# Adafruit_Ultimate_GPS.net
KiCad netlist of a schematic drawn in EAGLE
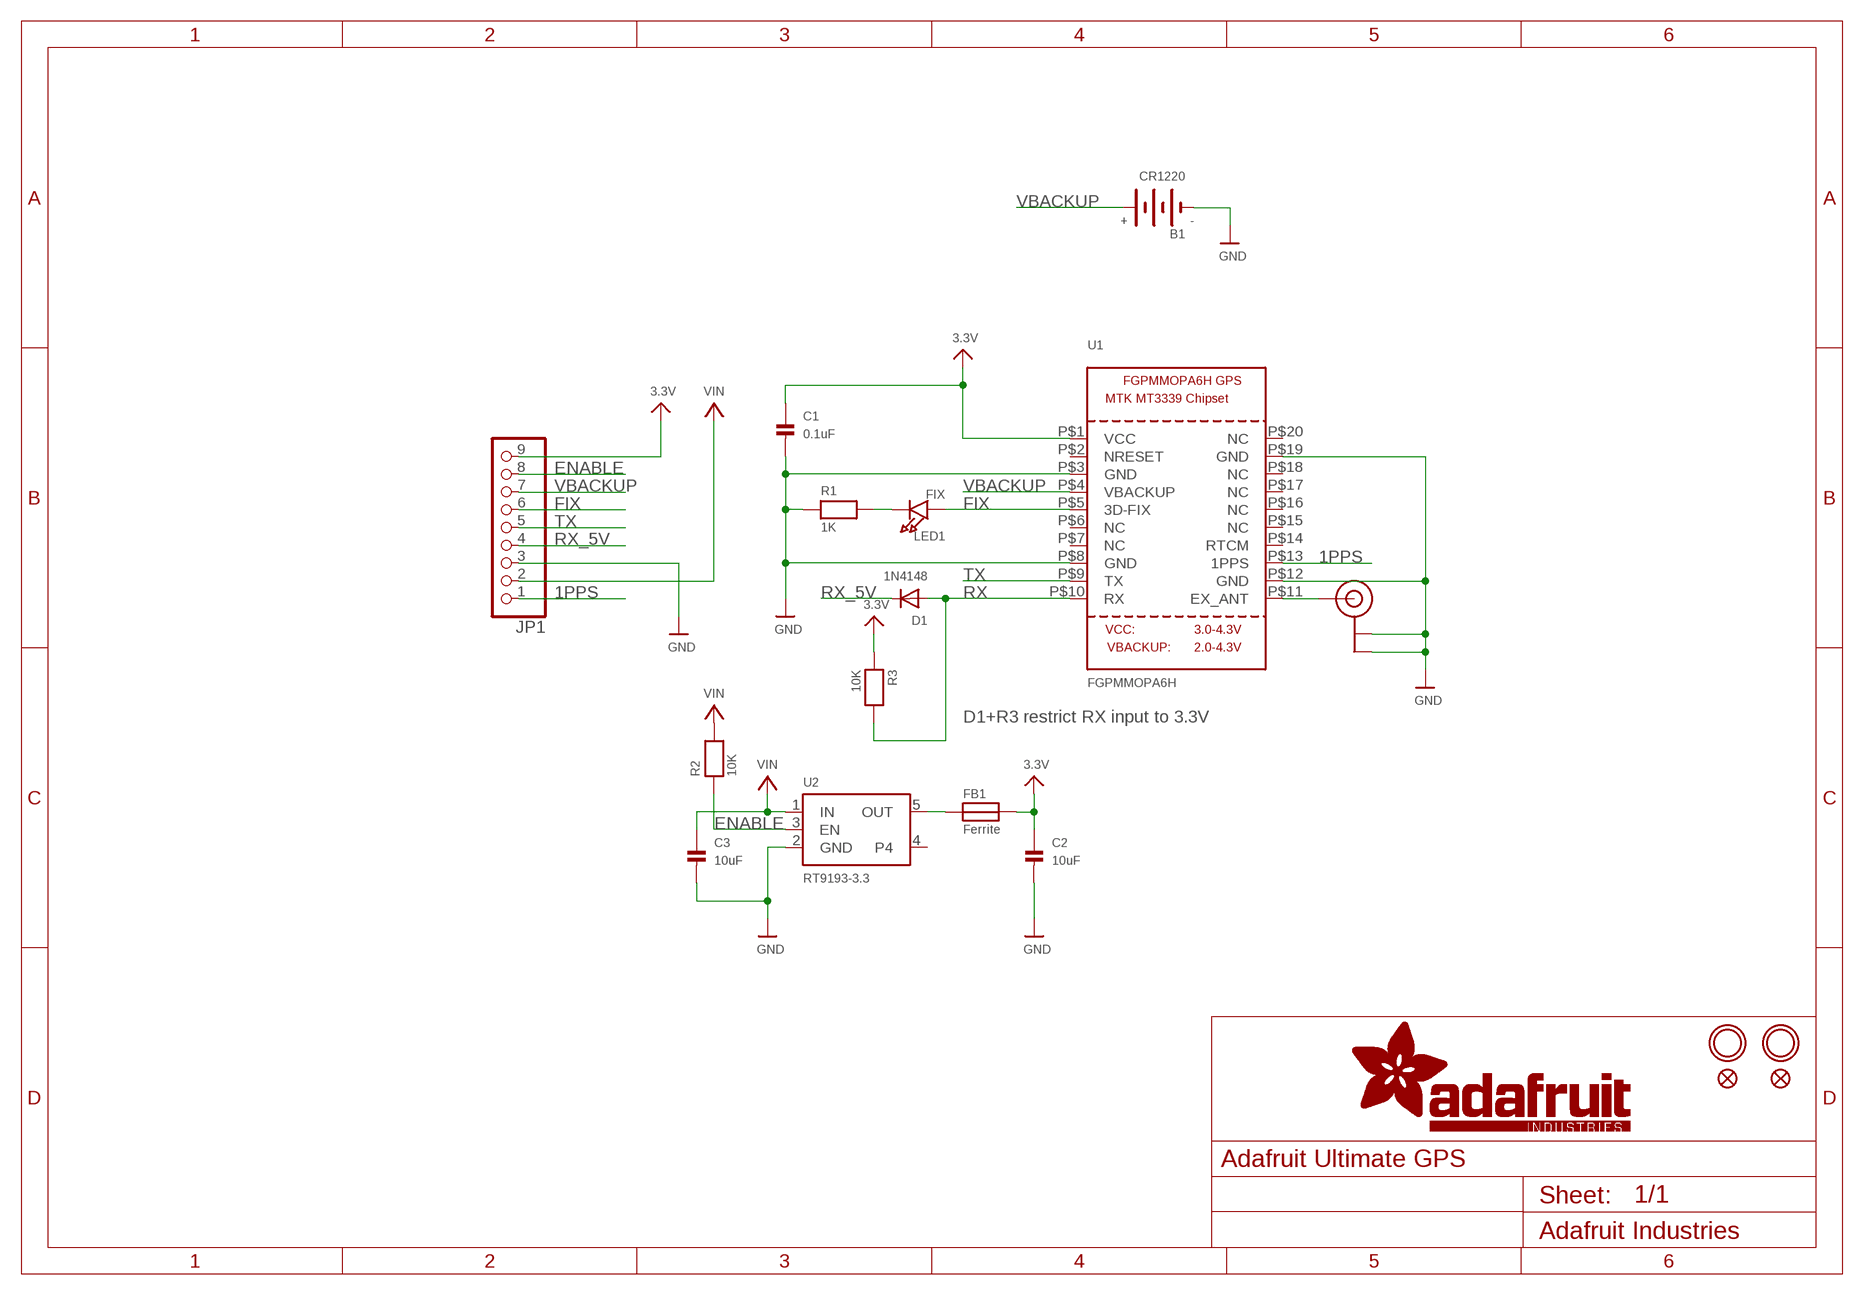
[diagram p0: schematic, sheet 1]

(export (version "E")
  (design (tool "Eeschema 10.0.6"))
  (components
    (comp (ref "B1")
      (value "CR1220")
      (footprint "eagle-import:CR1220")
      (libsource (lib "eagle-import") (part "BATTERYCR1220_SMT"))
    )
    (comp (ref "C1")
      (value "0.1uF")
      (footprint "eagle-import:0805")
      (libsource (lib "eagle-import") (part "CAP_CERAMIC0805"))
    )
    (comp (ref "C2")
      (value "10uF")
      (footprint "eagle-import:0805")
      (libsource (lib "eagle-import") (part "CAP_CERAMIC0805"))
    )
    (comp (ref "C3")
      (value "10uF")
      (footprint "eagle-import:0805")
      (libsource (lib "eagle-import") (part "CAP_CERAMIC0805"))
    )
    (comp (ref "D1")
      (value "1N4148")
      (footprint "eagle-import:SOD-323F")
      (libsource (lib "eagle-import") (part "DIODESOD-323F"))
    )
    (comp (ref "FB1")
      (value "Ferrite")
      (footprint "eagle-import:0805")
      (libsource (lib "eagle-import") (part "FERRITE0805"))
    )
    (comp (ref "FID1")
      (value "FIDUCIAL\"\"")
      (footprint "eagle-import:FIDUCIAL_1MM")
      (libsource (lib "eagle-import") (part "FIDUCIAL{dblquote}{dblquote}"))
    )
    (comp (ref "FID2")
      (value "FIDUCIAL\"\"")
      (footprint "eagle-import:FIDUCIAL_1MM")
      (libsource (lib "eagle-import") (part "FIDUCIAL{dblquote}{dblquote}"))
    )
    (comp (ref "JP1")
      (value "HEADER-1X970MIL")
      (footprint "eagle-import:1X09_ROUND_70")
      (libsource (lib "eagle-import") (part "HEADER-1X970MIL"))
    )
    (comp (ref "LED1")
      (value "FIX")
      (footprint "eagle-import:CHIPLED_0805")
      (libsource (lib "eagle-import") (part "LED0805"))
    )
    (comp (ref "R1")
      (value "1K")
      (footprint "eagle-import:0805")
      (libsource (lib "eagle-import") (part "RESISTOR0805"))
    )
    (comp (ref "R2")
      (value "10K")
      (footprint "eagle-import:0805")
      (libsource (lib "eagle-import") (part "RESISTOR0805"))
    )
    (comp (ref "R3")
      (value "10K")
      (footprint "eagle-import:0805")
      (libsource (lib "eagle-import") (part "RESISTOR0805"))
    )
    (comp (ref "U$8")
      (value "MOUNTINGHOLE2.0")
      (footprint "eagle-import:MOUNTINGHOLE_2.0_PLATED")
      (libsource (lib "eagle-import") (part "MOUNTINGHOLE2.0"))
    )
    (comp (ref "U$9")
      (value "MOUNTINGHOLE2.0")
      (footprint "eagle-import:MOUNTINGHOLE_2.0_PLATED")
      (libsource (lib "eagle-import") (part "MOUNTINGHOLE2.0"))
    )
    (comp (ref "U$20")
      (value "U.FL")
      (footprint "eagle-import:U.FL")
      (libsource (lib "eagle-import") (part "U.FL"))
    )
    (comp (ref "U1")
      (value "FGPMMOPA6H")
      (footprint "eagle-import:FGPMMOPA6H")
      (libsource (lib "eagle-import") (part "GPS_FGPMMOPA6H"))
    )
    (comp (ref "U2")
      (value "RT9193-3.3")
      (footprint "eagle-import:SOT23-5")
      (libsource (lib "eagle-import") (part "VREG_SOT23-5"))
    )
  )
  (nets
    (net (code "1") (name "/1PPS") (class "Default")
      (node (ref "JP1") (pin "1") (pinfunction "1_1") (pintype "passive"))
      (node (ref "U1") (pin "P$13") (pinfunction "1PPS_P$13") (pintype "bidirectional"))
    )
    (net (code "2") (name "/ENABLE") (class "Default")
      (node (ref "JP1") (pin "8") (pinfunction "8_8") (pintype "passive"))
      (node (ref "R2") (pin "1") (pinfunction "1_1") (pintype "passive"))
      (node (ref "U2") (pin "3") (pinfunction "EN_3") (pintype "bidirectional"))
    )
    (net (code "3") (name "/FIX") (class "Default")
      (node (ref "JP1") (pin "6") (pinfunction "6_6") (pintype "passive"))
      (node (ref "LED1") (pin "A") (pinfunction "A_A") (pintype "passive"))
      (node (ref "U1") (pin "P$5") (pinfunction "3D-FIX_P$5") (pintype "bidirectional"))
    )
    (net (code "4") (name "/RX") (class "Default")
      (node (ref "D1") (pin "A") (pinfunction "A_A") (pintype "passive"))
      (node (ref "R3") (pin "2") (pinfunction "2_2") (pintype "passive"))
      (node (ref "U1") (pin "P$10") (pinfunction "RX_P$10") (pintype "bidirectional"))
    )
    (net (code "5") (name "/RX_5V") (class "Default")
      (node (ref "D1") (pin "C") (pinfunction "C_C") (pintype "passive"))
      (node (ref "JP1") (pin "4") (pinfunction "4_4") (pintype "passive"))
    )
    (net (code "6") (name "/TX") (class "Default")
      (node (ref "JP1") (pin "5") (pinfunction "5_5") (pintype "passive"))
      (node (ref "U1") (pin "P$9") (pinfunction "TX_P$9") (pintype "bidirectional"))
    )
    (net (code "7") (name "/VBACKUP") (class "Default")
      (node (ref "B1") (pin "+$1") (pinfunction "+_+$1") (pintype "passive"))
      (node (ref "JP1") (pin "7") (pinfunction "7_7") (pintype "passive"))
      (node (ref "U1") (pin "P$4") (pinfunction "VBACKUP_P$4") (pintype "bidirectional"))
    )
    (net (code "8") (name "3.3V") (class "Default")
      (node (ref "C1") (pin "1") (pinfunction "P$1_1") (pintype "passive"))
      (node (ref "C2") (pin "1") (pinfunction "P$1_1") (pintype "passive"))
      (node (ref "FB1") (pin "2") (pinfunction "P$2_2") (pintype "bidirectional"))
      (node (ref "JP1") (pin "9") (pinfunction "9_9") (pintype "passive"))
      (node (ref "R3") (pin "1") (pinfunction "1_1") (pintype "passive"))
      (node (ref "U1") (pin "P$1") (pinfunction "VCC_P$1") (pintype "bidirectional"))
    )
    (net (code "9") (name "GND") (class "Default")
      (node (ref "B1") (pin "-") (pinfunction "-_-") (pintype "passive"))
      (node (ref "C1") (pin "2") (pinfunction "P$2_2") (pintype "passive"))
      (node (ref "C2") (pin "2") (pinfunction "P$2_2") (pintype "passive"))
      (node (ref "C3") (pin "2") (pinfunction "P$2_2") (pintype "passive"))
      (node (ref "JP1") (pin "3") (pinfunction "3_3") (pintype "passive"))
      (node (ref "R1") (pin "1") (pinfunction "1_1") (pintype "passive"))
      (node (ref "U$20") (pin "P$1") (pinfunction "GND_P$1") (pintype "bidirectional"))
      (node (ref "U$20") (pin "P$2") (pinfunction "GND_P$2") (pintype "bidirectional"))
      (node (ref "U1") (pin "P$12") (pinfunction "GND_P$12") (pintype "bidirectional"))
      (node (ref "U1") (pin "P$19") (pinfunction "GND_P$19") (pintype "bidirectional"))
      (node (ref "U1") (pin "P$3") (pinfunction "GND_P$3") (pintype "bidirectional"))
      (node (ref "U1") (pin "P$8") (pinfunction "GND_P$8") (pintype "bidirectional"))
      (node (ref "U2") (pin "2") (pinfunction "GND_2") (pintype "bidirectional"))
    )
    (net (code "10") (name "Net-(FB1-P$1)") (class "Default")
      (node (ref "FB1") (pin "1") (pinfunction "P$1_1") (pintype "bidirectional"))
      (node (ref "U2") (pin "5") (pinfunction "OUT_5") (pintype "bidirectional"))
    )
    (net (code "11") (name "Net-(LED1-PadC)") (class "Default")
      (node (ref "LED1") (pin "C") (pinfunction "C_C") (pintype "passive"))
      (node (ref "R1") (pin "2") (pinfunction "2_2") (pintype "passive"))
    )
    (net (code "12") (name "Net-(U$20-SIGNAL)") (class "Default")
      (node (ref "U$20") (pin "P$3") (pinfunction "SIGNAL_P$3") (pintype "bidirectional"))
      (node (ref "U1") (pin "P$11") (pinfunction "EX_ANT_P$11") (pintype "bidirectional"))
    )
    (net (code "13") (name "VIN") (class "Default")
      (node (ref "C3") (pin "1") (pinfunction "P$1_1") (pintype "passive"))
      (node (ref "JP1") (pin "2") (pinfunction "2_2") (pintype "passive"))
      (node (ref "R2") (pin "2") (pinfunction "2_2") (pintype "passive"))
      (node (ref "U2") (pin "1") (pinfunction "IN_1") (pintype "bidirectional"))
    )
    (net (code "14") (name "unconnected-(U1-NC-PadP$6)") (class "Default")
      (node (ref "U1") (pin "P$6") (pinfunction "NC_P$6") (pintype "bidirectional"))
    )
    (net (code "15") (name "unconnected-(U1-NC-PadP$7)") (class "Default")
      (node (ref "U1") (pin "P$7") (pinfunction "NC_P$7") (pintype "bidirectional"))
    )
    (net (code "16") (name "unconnected-(U1-NC-PadP$15)") (class "Default")
      (node (ref "U1") (pin "P$15") (pinfunction "NC_P$15") (pintype "bidirectional"))
    )
    (net (code "17") (name "unconnected-(U1-NC-PadP$16)") (class "Default")
      (node (ref "U1") (pin "P$16") (pinfunction "NC_P$16") (pintype "bidirectional"))
    )
    (net (code "18") (name "unconnected-(U1-NC-PadP$17)") (class "Default")
      (node (ref "U1") (pin "P$17") (pinfunction "NC_P$17") (pintype "bidirectional"))
    )
    (net (code "19") (name "unconnected-(U1-NC-PadP$18)") (class "Default")
      (node (ref "U1") (pin "P$18") (pinfunction "NC_P$18") (pintype "bidirectional"))
    )
    (net (code "20") (name "unconnected-(U1-NC-PadP$20)") (class "Default")
      (node (ref "U1") (pin "P$20") (pinfunction "NC_P$20") (pintype "bidirectional"))
    )
    (net (code "21") (name "unconnected-(U1-NRESET-PadP$2)") (class "Default")
      (node (ref "U1") (pin "P$2") (pinfunction "NRESET_P$2") (pintype "bidirectional"))
    )
    (net (code "22") (name "unconnected-(U1-RTCM-PadP$14)") (class "Default")
      (node (ref "U1") (pin "P$14") (pinfunction "RTCM_P$14") (pintype "bidirectional"))
    )
    (net (code "23") (name "unconnected-(U2-P4-Pad4)") (class "Default")
      (node (ref "U2") (pin "4") (pinfunction "P4_4") (pintype "bidirectional"))
    )
  )
)
